# Sensor.net
KiCad netlist of a schematic drawn in EAGLE
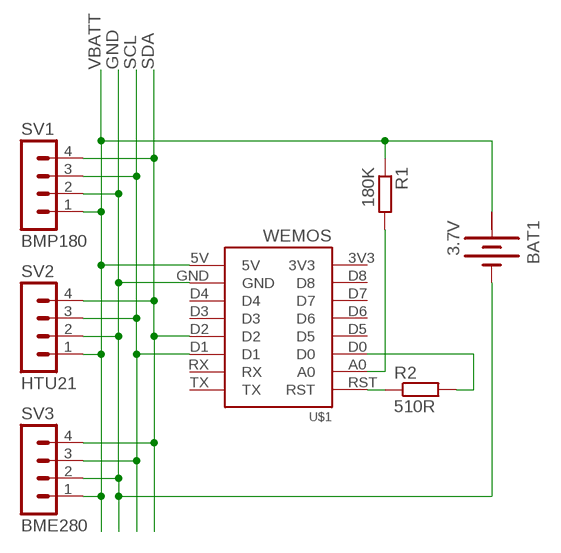
[diagram p0: schematic, sheet 1]

(export (version "E")
  (design (tool "Eeschema 10.0.6"))
  (components
    (comp (ref "BAT1")
      (value "3.7V")
      (footprint "eagle-import:BATTERY")
      (libsource (lib "eagle-import") (part "BATTERY"))
    )
    (comp (ref "R1")
      (value "180K")
      (footprint "eagle-import:0204_5")
      (libsource (lib "eagle-import") (part "R-EU_0204/5"))
    )
    (comp (ref "R2")
      (value "510R")
      (footprint "eagle-import:0204_5")
      (libsource (lib "eagle-import") (part "R-EU_0204/5"))
    )
    (comp (ref "SV1")
      (value "BMP180")
      (footprint "eagle-import:MA04-1")
      (libsource (lib "eagle-import") (part "MA04-1"))
    )
    (comp (ref "SV2")
      (value "HTU21")
      (footprint "eagle-import:MA04-1")
      (libsource (lib "eagle-import") (part "MA04-1"))
    )
    (comp (ref "SV3")
      (value "BME280")
      (footprint "eagle-import:MA04-1")
      (libsource (lib "eagle-import") (part "MA04-1"))
    )
    (comp (ref "U$1")
      (value "WEMOS")
      (footprint "eagle-import:WEMOS")
      (libsource (lib "eagle-import") (part "WEMOS"))
    )
  )
  (nets
    (net (code "1") (name "/+") (class "Default")
      (node (ref "BAT1") (pin "+@1") (pinfunction "+_+@1") (pintype "power_in"))
    )
    (net (code "2") (name "/GND") (class "Default")
      (node (ref "BAT1") (pin "-") (pinfunction "-_-") (pintype "power_in"))
      (node (ref "SV1") (pin "2") (pinfunction "2_2") (pintype "passive"))
      (node (ref "SV2") (pin "2") (pinfunction "2_2") (pintype "passive"))
      (node (ref "SV3") (pin "2") (pinfunction "2_2") (pintype "passive"))
      (node (ref "U$1") (pin "GND") (pinfunction "GND_GND") (pintype "bidirectional"))
    )
    (net (code "3") (name "/SCL") (class "Default")
      (node (ref "SV1") (pin "3") (pinfunction "3_3") (pintype "passive"))
      (node (ref "SV2") (pin "3") (pinfunction "3_3") (pintype "passive"))
      (node (ref "SV3") (pin "3") (pinfunction "3_3") (pintype "passive"))
      (node (ref "U$1") (pin "D1") (pinfunction "D1_D1") (pintype "bidirectional"))
    )
    (net (code "4") (name "/SDA") (class "Default")
      (node (ref "SV1") (pin "4") (pinfunction "4_4") (pintype "passive"))
      (node (ref "SV2") (pin "4") (pinfunction "4_4") (pintype "passive"))
      (node (ref "SV3") (pin "4") (pinfunction "4_4") (pintype "passive"))
      (node (ref "U$1") (pin "D2") (pinfunction "D2_D2") (pintype "bidirectional"))
    )
    (net (code "5") (name "/VBATT") (class "Default")
      (node (ref "BAT1") (pin "+") (pinfunction "+_+") (pintype "power_in"))
      (node (ref "R1") (pin "1") (pinfunction "1_1") (pintype "passive"))
      (node (ref "SV1") (pin "1") (pinfunction "1_1") (pintype "passive"))
      (node (ref "SV2") (pin "1") (pinfunction "1_1") (pintype "passive"))
      (node (ref "SV3") (pin "1") (pinfunction "1_1") (pintype "passive"))
      (node (ref "U$1") (pin "5V") (pinfunction "5V_5V") (pintype "bidirectional"))
    )
    (net (code "6") (name "Net-(R1-Pad2)") (class "Default")
      (node (ref "R1") (pin "2") (pinfunction "2_2") (pintype "passive"))
      (node (ref "U$1") (pin "A0") (pinfunction "A0_A0") (pintype "bidirectional"))
    )
    (net (code "7") (name "Net-(R2-Pad1)") (class "Default")
      (node (ref "R2") (pin "1") (pinfunction "1_1") (pintype "passive"))
      (node (ref "U$1") (pin "RST") (pinfunction "RST_RST") (pintype "bidirectional"))
    )
    (net (code "8") (name "Net-(R2-Pad2)") (class "Default")
      (node (ref "R2") (pin "2") (pinfunction "2_2") (pintype "passive"))
      (node (ref "U$1") (pin "D0") (pinfunction "D0_D0") (pintype "bidirectional"))
    )
    (net (code "9") (name "unconnected-(U$1-Pad3V3)") (class "Default")
      (node (ref "U$1") (pin "3V3") (pinfunction "3V3_3V3") (pintype "bidirectional"))
    )
    (net (code "10") (name "unconnected-(U$1-PadD3)") (class "Default")
      (node (ref "U$1") (pin "D3") (pinfunction "D3_D3") (pintype "bidirectional"))
    )
    (net (code "11") (name "unconnected-(U$1-PadD4)") (class "Default")
      (node (ref "U$1") (pin "D4") (pinfunction "D4_D4") (pintype "bidirectional"))
    )
    (net (code "12") (name "unconnected-(U$1-PadD5)") (class "Default")
      (node (ref "U$1") (pin "D5") (pinfunction "D5_D5") (pintype "bidirectional"))
    )
    (net (code "13") (name "unconnected-(U$1-PadD6)") (class "Default")
      (node (ref "U$1") (pin "D6") (pinfunction "D6_D6") (pintype "bidirectional"))
    )
    (net (code "14") (name "unconnected-(U$1-PadD7)") (class "Default")
      (node (ref "U$1") (pin "D7") (pinfunction "D7_D7") (pintype "bidirectional"))
    )
    (net (code "15") (name "unconnected-(U$1-PadD8)") (class "Default")
      (node (ref "U$1") (pin "D8") (pinfunction "D8_D8") (pintype "bidirectional"))
    )
    (net (code "16") (name "unconnected-(U$1-PadRX)") (class "Default")
      (node (ref "U$1") (pin "RX") (pinfunction "RX_RX") (pintype "bidirectional"))
    )
    (net (code "17") (name "unconnected-(U$1-PadTX)") (class "Default")
      (node (ref "U$1") (pin "TX") (pinfunction "TX_TX") (pintype "bidirectional"))
    )
  )
)
